# m8_2_6526.net
KiCad netlist of a schematic drawn in EAGLE
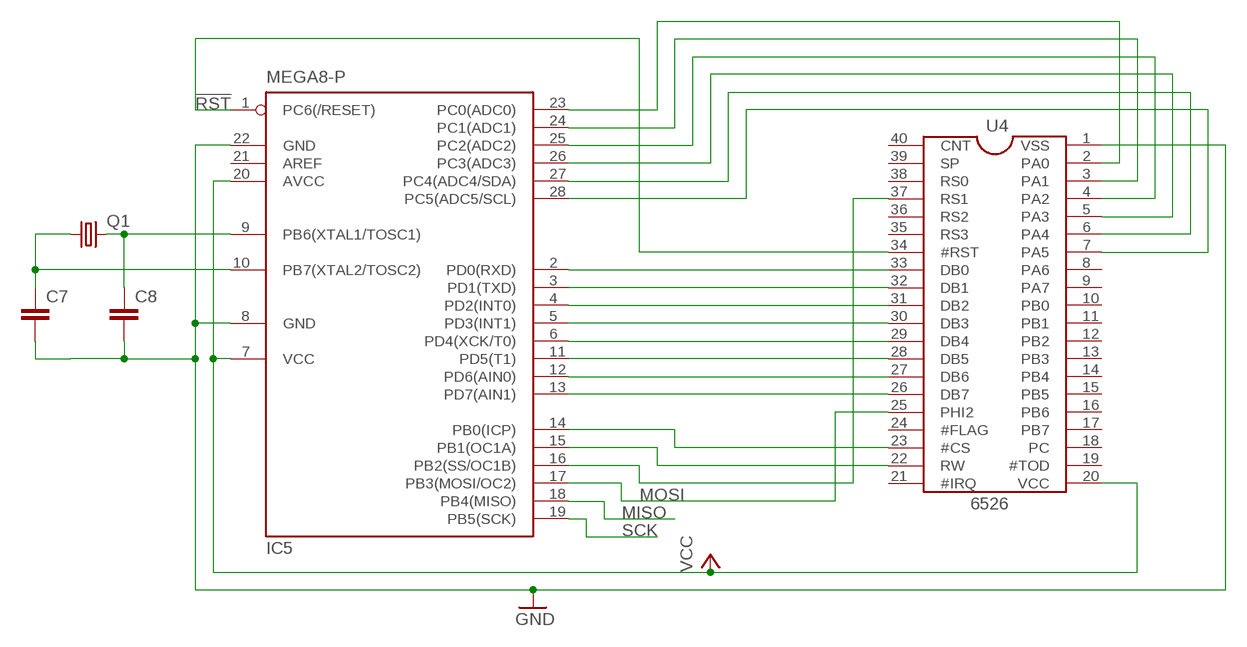
[diagram p0: schematic, sheet 1]

(export (version "E")
  (design (tool "Eeschema 10.0.6"))
  (components
    (comp (ref "C7")
      (value "C-EU025-025X050")
      (footprint "eagle-import:C025-025X050")
      (libsource (lib "eagle-import") (part "C-EU025-025X050"))
    )
    (comp (ref "C8")
      (value "C-EU025-025X050")
      (footprint "eagle-import:C025-025X050")
      (libsource (lib "eagle-import") (part "C-EU025-025X050"))
    )
    (comp (ref "IC5")
      (value "MEGA8-P")
      (footprint "eagle-import:DIL28-3")
      (libsource (lib "eagle-import") (part "MEGA8-P"))
    )
    (comp (ref "Q1")
      (value "CRYSTALHC49S")
      (footprint "eagle-import:HC49_S")
      (libsource (lib "eagle-import") (part "CRYSTALHC49S"))
    )
    (comp (ref "U4")
      (value "6526")
      (footprint "eagle-import:DIL40")
      (libsource (lib "eagle-import") (part "6526"))
    )
  )
  (nets
    (net (code "1") (name "/MISO") (class "Default")
      (node (ref "IC5") (pin "18") (pinfunction "PB4(MISO)_18") (pintype "bidirectional"))
    )
    (net (code "2") (name "/MOSI") (class "Default")
      (node (ref "IC5") (pin "17") (pinfunction "PB3(MOSI/OC2)_17") (pintype "bidirectional"))
      (node (ref "U4") (pin "25") (pinfunction "PHI2_25") (pintype "bidirectional"))
    )
    (net (code "3") (name "/SCK") (class "Default")
      (node (ref "IC5") (pin "19") (pinfunction "PB5(SCK)_19") (pintype "bidirectional"))
    )
    (net (code "4") (name "/~{RST}") (class "Default")
      (node (ref "IC5") (pin "1") (pinfunction "PC6(/RESET)_1") (pintype "bidirectional"))
      (node (ref "U4") (pin "34") (pinfunction "#RST_34") (pintype "bidirectional"))
    )
    (net (code "5") (name "GND") (class "Default")
      (node (ref "C7") (pin "2") (pinfunction "2_2") (pintype "passive"))
      (node (ref "C8") (pin "2") (pinfunction "2_2") (pintype "passive"))
      (node (ref "IC5") (pin "22") (pinfunction "GND_22") (pintype "power_in"))
      (node (ref "IC5") (pin "8") (pinfunction "GND_8") (pintype "power_in"))
      (node (ref "U4") (pin "1") (pinfunction "VSS_1") (pintype "bidirectional"))
    )
    (net (code "6") (name "Net-(IC5-PB0(ICP))") (class "Default")
      (node (ref "IC5") (pin "14") (pinfunction "PB0(ICP)_14") (pintype "bidirectional"))
      (node (ref "U4") (pin "23") (pinfunction "#CS_23") (pintype "bidirectional"))
    )
    (net (code "7") (name "Net-(IC5-PB1(OC1A))") (class "Default")
      (node (ref "IC5") (pin "15") (pinfunction "PB1(OC1A)_15") (pintype "bidirectional"))
      (node (ref "U4") (pin "22") (pinfunction "RW_22") (pintype "bidirectional"))
    )
    (net (code "8") (name "Net-(IC5-PB2(SS{slash}OC1B))") (class "Default")
      (node (ref "IC5") (pin "16") (pinfunction "PB2(SS/OC1B)_16") (pintype "bidirectional"))
      (node (ref "U4") (pin "37") (pinfunction "RS1_37") (pintype "bidirectional"))
    )
    (net (code "9") (name "Net-(IC5-PB6(XTAL1{slash}TOSC1))") (class "Default")
      (node (ref "C8") (pin "1") (pinfunction "1_1") (pintype "passive"))
      (node (ref "IC5") (pin "9") (pinfunction "PB6(XTAL1/TOSC1)_9") (pintype "bidirectional"))
      (node (ref "Q1") (pin "2") (pinfunction "2_2") (pintype "passive"))
    )
    (net (code "10") (name "Net-(IC5-PB7(XTAL2{slash}TOSC2))") (class "Default")
      (node (ref "C7") (pin "1") (pinfunction "1_1") (pintype "passive"))
      (node (ref "IC5") (pin "10") (pinfunction "PB7(XTAL2/TOSC2)_10") (pintype "bidirectional"))
      (node (ref "Q1") (pin "1") (pinfunction "1_1") (pintype "passive"))
    )
    (net (code "11") (name "Net-(IC5-PC0(ADC0))") (class "Default")
      (node (ref "IC5") (pin "23") (pinfunction "PC0(ADC0)_23") (pintype "bidirectional"))
      (node (ref "U4") (pin "2") (pinfunction "PA0_2") (pintype "bidirectional"))
    )
    (net (code "12") (name "Net-(IC5-PC1(ADC1))") (class "Default")
      (node (ref "IC5") (pin "24") (pinfunction "PC1(ADC1)_24") (pintype "bidirectional"))
      (node (ref "U4") (pin "3") (pinfunction "PA1_3") (pintype "bidirectional"))
    )
    (net (code "13") (name "Net-(IC5-PC2(ADC2))") (class "Default")
      (node (ref "IC5") (pin "25") (pinfunction "PC2(ADC2)_25") (pintype "bidirectional"))
      (node (ref "U4") (pin "4") (pinfunction "PA2_4") (pintype "bidirectional"))
    )
    (net (code "14") (name "Net-(IC5-PC3(ADC3))") (class "Default")
      (node (ref "IC5") (pin "26") (pinfunction "PC3(ADC3)_26") (pintype "bidirectional"))
      (node (ref "U4") (pin "5") (pinfunction "PA3_5") (pintype "bidirectional"))
    )
    (net (code "15") (name "Net-(IC5-PC4(ADC4{slash}SDA))") (class "Default")
      (node (ref "IC5") (pin "27") (pinfunction "PC4(ADC4/SDA)_27") (pintype "bidirectional"))
      (node (ref "U4") (pin "6") (pinfunction "PA4_6") (pintype "bidirectional"))
    )
    (net (code "16") (name "Net-(IC5-PC5(ADC5{slash}SCL))") (class "Default")
      (node (ref "IC5") (pin "28") (pinfunction "PC5(ADC5/SCL)_28") (pintype "bidirectional"))
      (node (ref "U4") (pin "7") (pinfunction "PA5_7") (pintype "bidirectional"))
    )
    (net (code "17") (name "Net-(IC5-PD0(RXD))") (class "Default")
      (node (ref "IC5") (pin "2") (pinfunction "PD0(RXD)_2") (pintype "bidirectional"))
      (node (ref "U4") (pin "33") (pinfunction "DB0_33") (pintype "bidirectional"))
    )
    (net (code "18") (name "Net-(IC5-PD1(TXD))") (class "Default")
      (node (ref "IC5") (pin "3") (pinfunction "PD1(TXD)_3") (pintype "bidirectional"))
      (node (ref "U4") (pin "32") (pinfunction "DB1_32") (pintype "bidirectional"))
    )
    (net (code "19") (name "Net-(IC5-PD2(INT0))") (class "Default")
      (node (ref "IC5") (pin "4") (pinfunction "PD2(INT0)_4") (pintype "bidirectional"))
      (node (ref "U4") (pin "31") (pinfunction "DB2_31") (pintype "bidirectional"))
    )
    (net (code "20") (name "Net-(IC5-PD3(INT1))") (class "Default")
      (node (ref "IC5") (pin "5") (pinfunction "PD3(INT1)_5") (pintype "bidirectional"))
      (node (ref "U4") (pin "30") (pinfunction "DB3_30") (pintype "bidirectional"))
    )
    (net (code "21") (name "Net-(IC5-PD4(XCK{slash}T0))") (class "Default")
      (node (ref "IC5") (pin "6") (pinfunction "PD4(XCK/T0)_6") (pintype "bidirectional"))
      (node (ref "U4") (pin "29") (pinfunction "DB4_29") (pintype "bidirectional"))
    )
    (net (code "22") (name "Net-(IC5-PD5(T1))") (class "Default")
      (node (ref "IC5") (pin "11") (pinfunction "PD5(T1)_11") (pintype "bidirectional"))
      (node (ref "U4") (pin "28") (pinfunction "DB5_28") (pintype "bidirectional"))
    )
    (net (code "23") (name "Net-(IC5-PD6(AIN0))") (class "Default")
      (node (ref "IC5") (pin "12") (pinfunction "PD6(AIN0)_12") (pintype "bidirectional"))
      (node (ref "U4") (pin "27") (pinfunction "DB6_27") (pintype "bidirectional"))
    )
    (net (code "24") (name "Net-(IC5-PD7(AIN1))") (class "Default")
      (node (ref "IC5") (pin "13") (pinfunction "PD7(AIN1)_13") (pintype "bidirectional"))
      (node (ref "U4") (pin "26") (pinfunction "DB7_26") (pintype "bidirectional"))
    )
    (net (code "25") (name "VCC") (class "Default")
      (node (ref "IC5") (pin "20") (pinfunction "AVCC_20") (pintype "power_in"))
      (node (ref "IC5") (pin "7") (pinfunction "VCC_7") (pintype "power_in"))
      (node (ref "U4") (pin "20") (pinfunction "VCC_20") (pintype "bidirectional"))
    )
    (net (code "26") (name "unconnected-(IC5-AREF-Pad21)") (class "Default")
      (node (ref "IC5") (pin "21") (pinfunction "AREF_21") (pintype "passive"))
    )
    (net (code "27") (name "unconnected-(U4-#FLAG-Pad24)") (class "Default")
      (node (ref "U4") (pin "24") (pinfunction "#FLAG_24") (pintype "bidirectional"))
    )
    (net (code "28") (name "unconnected-(U4-#IRQ-Pad21)") (class "Default")
      (node (ref "U4") (pin "21") (pinfunction "#IRQ_21") (pintype "bidirectional"))
    )
    (net (code "29") (name "unconnected-(U4-#TOD-Pad19)") (class "Default")
      (node (ref "U4") (pin "19") (pinfunction "#TOD_19") (pintype "bidirectional"))
    )
    (net (code "30") (name "unconnected-(U4-CNT-Pad40)") (class "Default")
      (node (ref "U4") (pin "40") (pinfunction "CNT_40") (pintype "bidirectional"))
    )
    (net (code "31") (name "unconnected-(U4-PA6-Pad8)") (class "Default")
      (node (ref "U4") (pin "8") (pinfunction "PA6_8") (pintype "bidirectional"))
    )
    (net (code "32") (name "unconnected-(U4-PA7-Pad9)") (class "Default")
      (node (ref "U4") (pin "9") (pinfunction "PA7_9") (pintype "bidirectional"))
    )
    (net (code "33") (name "unconnected-(U4-PB0-Pad10)") (class "Default")
      (node (ref "U4") (pin "10") (pinfunction "PB0_10") (pintype "bidirectional"))
    )
    (net (code "34") (name "unconnected-(U4-PB1-Pad11)") (class "Default")
      (node (ref "U4") (pin "11") (pinfunction "PB1_11") (pintype "bidirectional"))
    )
    (net (code "35") (name "unconnected-(U4-PB2-Pad12)") (class "Default")
      (node (ref "U4") (pin "12") (pinfunction "PB2_12") (pintype "bidirectional"))
    )
    (net (code "36") (name "unconnected-(U4-PB3-Pad13)") (class "Default")
      (node (ref "U4") (pin "13") (pinfunction "PB3_13") (pintype "bidirectional"))
    )
    (net (code "37") (name "unconnected-(U4-PB4-Pad14)") (class "Default")
      (node (ref "U4") (pin "14") (pinfunction "PB4_14") (pintype "bidirectional"))
    )
    (net (code "38") (name "unconnected-(U4-PB5-Pad15)") (class "Default")
      (node (ref "U4") (pin "15") (pinfunction "PB5_15") (pintype "bidirectional"))
    )
    (net (code "39") (name "unconnected-(U4-PB6-Pad16)") (class "Default")
      (node (ref "U4") (pin "16") (pinfunction "PB6_16") (pintype "bidirectional"))
    )
    (net (code "40") (name "unconnected-(U4-PB7-Pad17)") (class "Default")
      (node (ref "U4") (pin "17") (pinfunction "PB7_17") (pintype "bidirectional"))
    )
    (net (code "41") (name "unconnected-(U4-PC-Pad18)") (class "Default")
      (node (ref "U4") (pin "18") (pinfunction "PC_18") (pintype "bidirectional"))
    )
    (net (code "42") (name "unconnected-(U4-RS0-Pad38)") (class "Default")
      (node (ref "U4") (pin "38") (pinfunction "RS0_38") (pintype "bidirectional"))
    )
    (net (code "43") (name "unconnected-(U4-RS2-Pad36)") (class "Default")
      (node (ref "U4") (pin "36") (pinfunction "RS2_36") (pintype "bidirectional"))
    )
    (net (code "44") (name "unconnected-(U4-RS3-Pad35)") (class "Default")
      (node (ref "U4") (pin "35") (pinfunction "RS3_35") (pintype "bidirectional"))
    )
    (net (code "45") (name "unconnected-(U4-SP-Pad39)") (class "Default")
      (node (ref "U4") (pin "39") (pinfunction "SP_39") (pintype "bidirectional"))
    )
  )
)
